# STM32L441CE.net
KiCad netlist of a schematic drawn in EAGLE
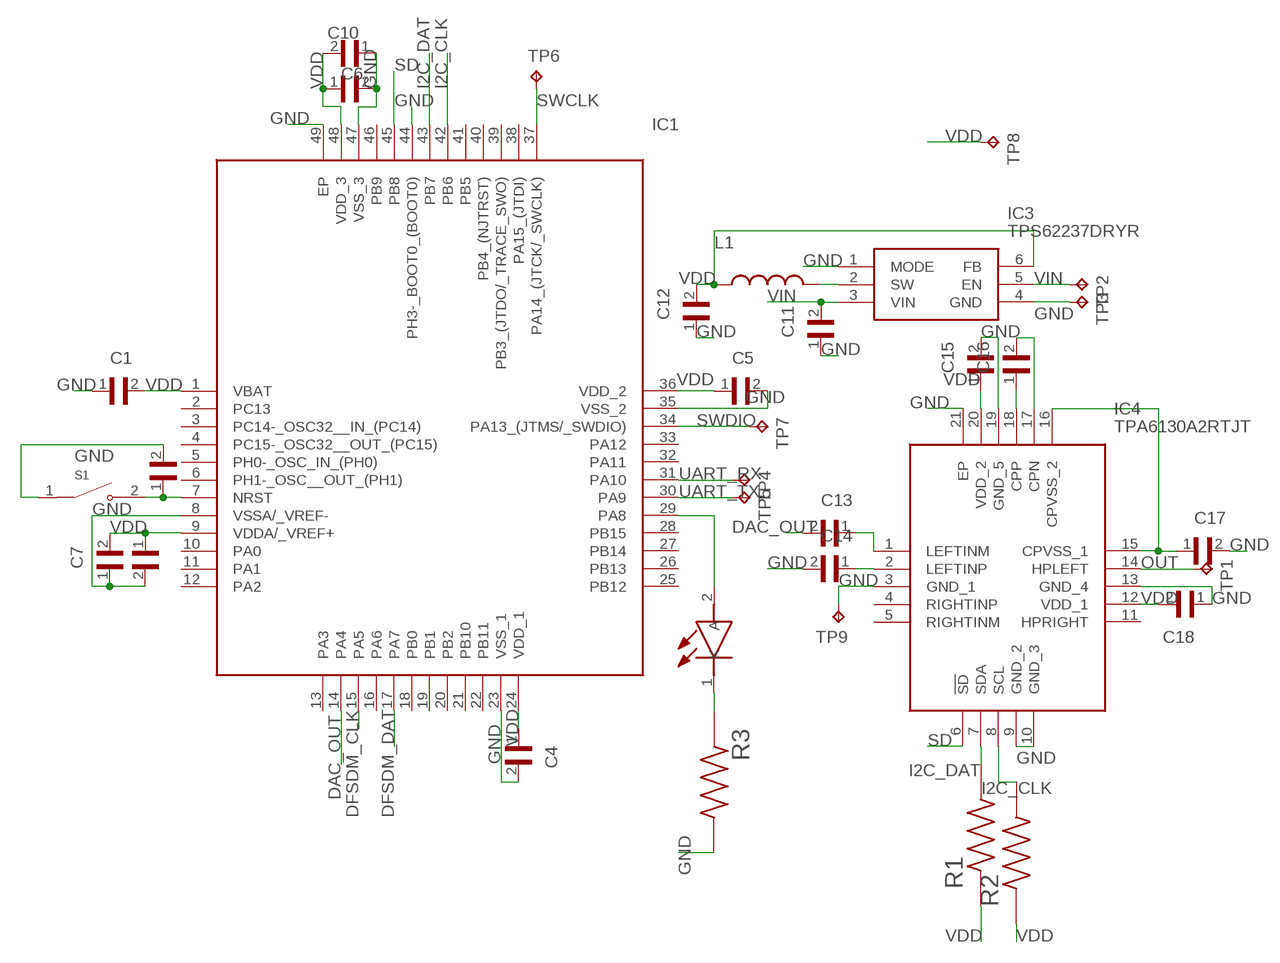
[diagram p0: schematic, sheet 1]
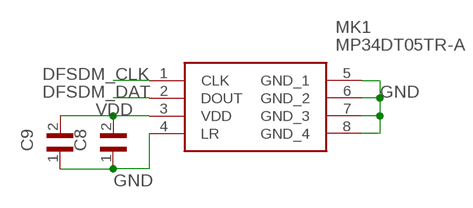
[diagram p1: schematic, sheet 2]

(export (version "E")
  (design (tool "Eeschema 10.0.6"))
  (components
    (comp (ref "C1")
      (value "GRM033C80J104KE15D")
      (footprint "eagle-import:CAPC0603X33N")
      (fields (field (name "DIGI-KEY_PART_NUMBER") "490-10390-1-ND") (field (name "MF") "Murata Electronics"))
      (libsource (lib "eagle-import") (part "GRM033C80J104KE15D"))
    )
    (comp (ref "C2")
      (value "GRM033C80J104KE15D")
      (footprint "eagle-import:CAPC0603X33N")
      (fields (field (name "DIGI-KEY_PART_NUMBER") "490-10390-1-ND") (field (name "MF") "Murata Electronics"))
      (libsource (lib "eagle-import") (part "GRM033C80J104KE15D"))
    )
    (comp (ref "C3")
      (value "GRM033C80J104KE15D")
      (footprint "eagle-import:CAPC0603X33N")
      (fields (field (name "DIGI-KEY_PART_NUMBER") "490-10390-1-ND") (field (name "MF") "Murata Electronics"))
      (libsource (lib "eagle-import") (part "GRM033C80J104KE15D"))
    )
    (comp (ref "C4")
      (value "GRM033C80J104KE15D")
      (footprint "eagle-import:CAPC0603X33N")
      (fields (field (name "DIGI-KEY_PART_NUMBER") "490-10390-1-ND") (field (name "MF") "Murata Electronics"))
      (libsource (lib "eagle-import") (part "GRM033C80J104KE15D"))
    )
    (comp (ref "C5")
      (value "GRM033C80J104KE15D")
      (footprint "eagle-import:CAPC0603X33N")
      (fields (field (name "DIGI-KEY_PART_NUMBER") "490-10390-1-ND") (field (name "MF") "Murata Electronics"))
      (libsource (lib "eagle-import") (part "GRM033C80J104KE15D"))
    )
    (comp (ref "C6")
      (value "GRM033C80J104KE15D")
      (footprint "eagle-import:CAPC0603X33N")
      (fields (field (name "DIGI-KEY_PART_NUMBER") "490-10390-1-ND") (field (name "MF") "Murata Electronics"))
      (libsource (lib "eagle-import") (part "GRM033C80J104KE15D"))
    )
    (comp (ref "C7")
      (value "JMK105C6105KV-F")
      (footprint "eagle-import:CAPC1005X55N")
      (fields (field (name "DIGI-KEY_PART_NUMBER") "587-3381-1-ND") (field (name "MF") "Taiyo Yuden"))
      (libsource (lib "eagle-import") (part "JMK105C6105KV-F"))
    )
    (comp (ref "C10")
      (value "GRM155R60J475ME47D")
      (footprint "eagle-import:CAPC1005X60N")
      (fields (field (name "DIGI-KEY_PART_NUMBER") "490-5915-1-ND") (field (name "MF") "Murata"))
      (libsource (lib "eagle-import") (part "GRM155R60J475ME47D"))
    )
    (comp (ref "C11")
      (value "GRM155R60J225KE95D")
      (footprint "eagle-import:CAPC1005X55N")
      (fields (field (name "DIGI-KEY_PART_NUMBER") "490-12532-1-ND") (field (name "MF") "Murata"))
      (libsource (lib "eagle-import") (part "GRM155R60J225KE95D"))
    )
    (comp (ref "C12")
      (value "GRM155R60J475ME47D")
      (footprint "eagle-import:CAPC1005X60N")
      (fields (field (name "DIGI-KEY_PART_NUMBER") "490-5915-1-ND") (field (name "MF") "Murata"))
      (libsource (lib "eagle-import") (part "GRM155R60J475ME47D"))
    )
    (comp (ref "C13")
      (value "CC0402KRX5R5BB474")
      (footprint "eagle-import:CAPC1005X55N")
      (fields (field (name "DIGI-KEY_PART_NUMBER") "311-1684-1-ND") (field (name "MF") "Yageo"))
      (libsource (lib "eagle-import") (part "CC0402KRX5R5BB474"))
    )
    (comp (ref "C14")
      (value "CC0402KRX5R5BB474")
      (footprint "eagle-import:CAPC1005X55N")
      (fields (field (name "DIGI-KEY_PART_NUMBER") "311-1684-1-ND") (field (name "MF") "Yageo"))
      (libsource (lib "eagle-import") (part "CC0402KRX5R5BB474"))
    )
    (comp (ref "C15")
      (value "JMK105C6105KV-F")
      (footprint "eagle-import:CAPC1005X55N")
      (fields (field (name "DIGI-KEY_PART_NUMBER") "587-3381-1-ND") (field (name "MF") "Taiyo Yuden"))
      (libsource (lib "eagle-import") (part "JMK105C6105KV-F"))
    )
    (comp (ref "C16")
      (value "JMK105C6105KV-F")
      (footprint "eagle-import:CAPC1005X55N")
      (fields (field (name "DIGI-KEY_PART_NUMBER") "587-3381-1-ND") (field (name "MF") "Taiyo Yuden"))
      (libsource (lib "eagle-import") (part "JMK105C6105KV-F"))
    )
    (comp (ref "C17")
      (value "JMK105C6105KV-F")
      (footprint "eagle-import:CAPC1005X55N")
      (fields (field (name "DIGI-KEY_PART_NUMBER") "587-3381-1-ND") (field (name "MF") "Taiyo Yuden"))
      (libsource (lib "eagle-import") (part "JMK105C6105KV-F"))
    )
    (comp (ref "C18")
      (value "JMK105C6105KV-F")
      (footprint "eagle-import:CAPC1005X55N")
      (fields (field (name "DIGI-KEY_PART_NUMBER") "587-3381-1-ND") (field (name "MF") "Taiyo Yuden"))
      (libsource (lib "eagle-import") (part "JMK105C6105KV-F"))
    )
    (comp (ref "IC1")
      (value "STM32L451CEU6")
      (footprint "eagle-import:QFN50P700X700X60-49N")
      (fields (field (name "MOUSER_PART_NUMBER") "511-STM32L451CEU6"))
      (libsource (lib "eagle-import") (part "STM32L451CEU6"))
    )
    (comp (ref "IC3")
      (value "TPS62237DRYR")
      (footprint "eagle-import:SON50P100X145X60-6N")
      (fields (field (name "MOUSER_PART_NUMBER") "595-TPS62237DRYR"))
      (libsource (lib "eagle-import") (part "TPS62237DRYR"))
    )
    (comp (ref "IC4")
      (value "TPA6130A2RTJT")
      (footprint "eagle-import:QFN50P400X400X80-21N")
      (fields (field (name "MOUSER_PART_NUMBER") "595-TPA6130A2RTJT"))
      (libsource (lib "eagle-import") (part "TPA6130A2RTJT"))
    )
    (comp (ref "L1")
      (value "LQM21PN2R2MC0D")
      (footprint "eagle-import:INDC2012X55N")
      (fields (field (name "DIGI-KEY_PART_NUMBER") "490-4994-1-ND") (field (name "MF") "Murata"))
      (libsource (lib "eagle-import") (part "LQM21PN2R2MC0D"))
    )
    (comp (ref "LED1")
      (value "VLMS1500-GS08")
      (footprint "eagle-import:VLMG1500GS08")
      (fields (field (name "MOUSER_PART_NUMBER") "78-VLMS1500-GS08"))
      (libsource (lib "eagle-import") (part "VLMS1500-GS08"))
    )
    (comp (ref "R1")
      (value "ERJ-1GNJ222C")
      (footprint "eagle-import:RESC0603X26N")
      (fields (field (name "DIGI-KEY_PART_NUMBER") "P123277CT-ND") (field (name "MF") "Panasonic"))
      (libsource (lib "eagle-import") (part "ERJ-1GNJ222C"))
    )
    (comp (ref "R2")
      (value "ERJ-1GNJ222C")
      (footprint "eagle-import:RESC0603X26N")
      (fields (field (name "DIGI-KEY_PART_NUMBER") "P123277CT-ND") (field (name "MF") "Panasonic"))
      (libsource (lib "eagle-import") (part "ERJ-1GNJ222C"))
    )
    (comp (ref "R3")
      (value "ERJ-1GNJ222C")
      (footprint "eagle-import:RESC0603X26N")
      (fields (field (name "DIGI-KEY_PART_NUMBER") "P123277CT-ND") (field (name "MF") "Panasonic"))
      (libsource (lib "eagle-import") (part "ERJ-1GNJ222C"))
    )
    (comp (ref "S1")
      (value "B3U-1000P")
      (footprint "eagle-import:SW_B3U-1000P")
      (fields (field (name "DIGI-KEY_PART_NUMBER") "SW1020CT-ND") (field (name "MF") "Omron"))
      (libsource (lib "eagle-import") (part "B3U-1000P"))
    )
    (comp (ref "TP1")
      (value "TPTP11R")
      (footprint "eagle-import:TP11R")
      (libsource (lib "eagle-import") (part "TPTP11R"))
    )
    (comp (ref "TP2")
      (value "TPTP11R")
      (footprint "eagle-import:TP11R")
      (libsource (lib "eagle-import") (part "TPTP11R"))
    )
    (comp (ref "TP3")
      (value "TPTP11R")
      (footprint "eagle-import:TP11R")
      (libsource (lib "eagle-import") (part "TPTP11R"))
    )
    (comp (ref "TP4")
      (value "TPTP11R")
      (footprint "eagle-import:TP11R")
      (libsource (lib "eagle-import") (part "TPTP11R"))
    )
    (comp (ref "TP5")
      (value "TPTP11R")
      (footprint "eagle-import:TP11R")
      (libsource (lib "eagle-import") (part "TPTP11R"))
    )
    (comp (ref "TP6")
      (value "TPTP11R")
      (footprint "eagle-import:TP11R")
      (libsource (lib "eagle-import") (part "TPTP11R"))
    )
    (comp (ref "TP7")
      (value "TPTP11R")
      (footprint "eagle-import:TP11R")
      (libsource (lib "eagle-import") (part "TPTP11R"))
    )
    (comp (ref "TP8")
      (value "TPTP11R")
      (footprint "eagle-import:TP11R")
      (libsource (lib "eagle-import") (part "TPTP11R"))
    )
    (comp (ref "TP9")
      (value "TPTP11R")
      (footprint "eagle-import:TP11R")
      (libsource (lib "eagle-import") (part "TPTP11R"))
    )
    (comp (ref "C8")
      (value "JMK105C6105KV-F")
      (footprint "eagle-import:CAPC1005X55N")
      (fields (field (name "DIGI-KEY_PART_NUMBER") "587-3381-1-ND") (field (name "MF") "Taiyo Yuden"))
      (libsource (lib "eagle-import") (part "JMK105C6105KV-F"))
    )
    (comp (ref "C9")
      (value "GRM033C80J104KE15D")
      (footprint "eagle-import:CAPC0603X33N")
      (fields (field (name "DIGI-KEY_PART_NUMBER") "490-10390-1-ND") (field (name "MF") "Murata Electronics"))
      (libsource (lib "eagle-import") (part "GRM033C80J104KE15D"))
    )
    (comp (ref "MK1")
      (value "MP34DT05TR-A")
      (footprint "eagle-import:MP34DT05TRA")
      (fields (field (name "MOUSER_PART_NUMBER") "511-MP34DT05TR-A"))
      (libsource (lib "eagle-import") (part "MP34DT05TR-A"))
    )
  )
  (nets
    (net (code "1") (name "DAC_OUT") (class "Default")
      (node (ref "C13") (pin "2") (pinfunction "2_2") (pintype "passive"))
      (node (ref "IC1") (pin "14") (pinfunction "PA4_14") (pintype "bidirectional"))
    )
    (net (code "2") (name "DFSDM_CLK") (class "Default")
      (node (ref "IC1") (pin "15") (pinfunction "PA5_15") (pintype "bidirectional"))
      (node (ref "MK1") (pin "1") (pinfunction "CLK_1") (pintype "bidirectional"))
    )
    (net (code "3") (name "DFSDM_DAT") (class "Default")
      (node (ref "IC1") (pin "17") (pinfunction "PA7_17") (pintype "bidirectional"))
      (node (ref "MK1") (pin "2") (pinfunction "DOUT_2") (pintype "bidirectional"))
    )
    (net (code "4") (name "GND") (class "Default")
      (node (ref "C1") (pin "1") (pinfunction "1_1") (pintype "passive"))
      (node (ref "C10") (pin "1") (pinfunction "1_1") (pintype "passive"))
      (node (ref "C11") (pin "1") (pinfunction "1_1") (pintype "passive"))
      (node (ref "C12") (pin "1") (pinfunction "1_1") (pintype "passive"))
      (node (ref "C14") (pin "2") (pinfunction "2_2") (pintype "passive"))
      (node (ref "C15") (pin "2") (pinfunction "2_2") (pintype "passive"))
      (node (ref "C17") (pin "2") (pinfunction "2_2") (pintype "passive"))
      (node (ref "C18") (pin "1") (pinfunction "1_1") (pintype "passive"))
      (node (ref "C2") (pin "2") (pinfunction "2_2") (pintype "passive"))
      (node (ref "C3") (pin "2") (pinfunction "2_2") (pintype "passive"))
      (node (ref "C4") (pin "2") (pinfunction "2_2") (pintype "passive"))
      (node (ref "C5") (pin "2") (pinfunction "2_2") (pintype "passive"))
      (node (ref "C6") (pin "2") (pinfunction "2_2") (pintype "passive"))
      (node (ref "C7") (pin "1") (pinfunction "1_1") (pintype "passive"))
      (node (ref "C8") (pin "1") (pinfunction "1_1") (pintype "passive"))
      (node (ref "C9") (pin "1") (pinfunction "1_1") (pintype "passive"))
      (node (ref "IC1") (pin "23") (pinfunction "VSS_1_23") (pintype "bidirectional"))
      (node (ref "IC1") (pin "35") (pinfunction "VSS_2_35") (pintype "bidirectional"))
      (node (ref "IC1") (pin "44") (pinfunction "PH3-_BOOT0_(BOOT0)_44") (pintype "bidirectional"))
      (node (ref "IC1") (pin "47") (pinfunction "VSS_3_47") (pintype "bidirectional"))
      (node (ref "IC1") (pin "49") (pinfunction "EP_49") (pintype "bidirectional"))
      (node (ref "IC1") (pin "8") (pinfunction "VSSA/_VREF-_8") (pintype "bidirectional"))
      (node (ref "IC3") (pin "1") (pinfunction "MODE_1") (pintype "bidirectional"))
      (node (ref "IC3") (pin "4") (pinfunction "GND_4") (pintype "bidirectional"))
      (node (ref "IC4") (pin "10") (pinfunction "GND_3_10") (pintype "bidirectional"))
      (node (ref "IC4") (pin "13") (pinfunction "GND_4_13") (pintype "bidirectional"))
      (node (ref "IC4") (pin "19") (pinfunction "GND_5_19") (pintype "bidirectional"))
      (node (ref "IC4") (pin "21") (pinfunction "EP_21") (pintype "bidirectional"))
      (node (ref "IC4") (pin "3") (pinfunction "GND_1_3") (pintype "bidirectional"))
      (node (ref "IC4") (pin "9") (pinfunction "GND_2_9") (pintype "bidirectional"))
      (node (ref "MK1") (pin "4") (pinfunction "LR_4") (pintype "bidirectional"))
      (node (ref "MK1") (pin "5") (pinfunction "GND_1_5") (pintype "bidirectional"))
      (node (ref "MK1") (pin "6") (pinfunction "GND_2_6") (pintype "bidirectional"))
      (node (ref "MK1") (pin "7") (pinfunction "GND_3_7") (pintype "bidirectional"))
      (node (ref "MK1") (pin "8") (pinfunction "GND_4_8") (pintype "bidirectional"))
      (node (ref "R3") (pin "2") (pinfunction "2_2") (pintype "passive"))
      (node (ref "S1") (pin "1") (pinfunction "1_1") (pintype "passive"))
      (node (ref "TP3") (pin "TP") (pinfunction "TP_TP") (pintype "input"))
      (node (ref "TP9") (pin "TP") (pinfunction "TP_TP") (pintype "input"))
    )
    (net (code "5") (name "I2C_CLK") (class "Default")
      (node (ref "IC1") (pin "42") (pinfunction "PB6_42") (pintype "bidirectional"))
      (node (ref "IC4") (pin "8") (pinfunction "SCL_8") (pintype "bidirectional"))
      (node (ref "R2") (pin "2") (pinfunction "2_2") (pintype "passive"))
    )
    (net (code "6") (name "I2C_DAT") (class "Default")
      (node (ref "IC1") (pin "43") (pinfunction "PB7_43") (pintype "bidirectional"))
      (node (ref "IC4") (pin "7") (pinfunction "SDA_7") (pintype "bidirectional"))
      (node (ref "R1") (pin "2") (pinfunction "2_2") (pintype "passive"))
    )
    (net (code "7") (name "Net-(IC1-NRST)") (class "Default")
      (node (ref "C2") (pin "1") (pinfunction "1_1") (pintype "passive"))
      (node (ref "IC1") (pin "7") (pinfunction "NRST_7") (pintype "bidirectional"))
      (node (ref "S1") (pin "2") (pinfunction "2_2") (pintype "passive"))
    )
    (net (code "8") (name "Net-(IC1-PA8)") (class "Default")
      (node (ref "IC1") (pin "29") (pinfunction "PA8_29") (pintype "bidirectional"))
      (node (ref "LED1") (pin "2") (pinfunction "A_2") (pintype "bidirectional"))
    )
    (net (code "9") (name "Net-(IC3-SW)") (class "Default")
      (node (ref "IC3") (pin "2") (pinfunction "SW_2") (pintype "bidirectional"))
      (node (ref "L1") (pin "2") (pinfunction "2_2") (pintype "passive"))
    )
    (net (code "10") (name "Net-(IC4-CPN)") (class "Default")
      (node (ref "C16") (pin "2") (pinfunction "2_2") (pintype "passive"))
      (node (ref "IC4") (pin "17") (pinfunction "CPN_17") (pintype "bidirectional"))
    )
    (net (code "11") (name "Net-(IC4-CPP)") (class "Default")
      (node (ref "C16") (pin "1") (pinfunction "1_1") (pintype "passive"))
      (node (ref "IC4") (pin "18") (pinfunction "CPP_18") (pintype "bidirectional"))
    )
    (net (code "12") (name "Net-(IC4-CPVSS_1)") (class "Default")
      (node (ref "C17") (pin "1") (pinfunction "1_1") (pintype "passive"))
      (node (ref "IC4") (pin "15") (pinfunction "CPVSS_1_15") (pintype "bidirectional"))
      (node (ref "IC4") (pin "16") (pinfunction "CPVSS_2_16") (pintype "bidirectional"))
    )
    (net (code "13") (name "Net-(IC4-LEFTINM)") (class "Default")
      (node (ref "C13") (pin "1") (pinfunction "1_1") (pintype "passive"))
      (node (ref "IC4") (pin "1") (pinfunction "LEFTINM_1") (pintype "bidirectional"))
    )
    (net (code "14") (name "Net-(IC4-LEFTINP)") (class "Default")
      (node (ref "C14") (pin "1") (pinfunction "1_1") (pintype "passive"))
      (node (ref "IC4") (pin "2") (pinfunction "LEFTINP_2") (pintype "bidirectional"))
    )
    (net (code "15") (name "Net-(LED1-K)") (class "Default")
      (node (ref "LED1") (pin "1") (pinfunction "K_1") (pintype "bidirectional"))
      (node (ref "R3") (pin "1") (pinfunction "1_1") (pintype "passive"))
    )
    (net (code "16") (name "OUT") (class "Default")
      (node (ref "IC4") (pin "14") (pinfunction "HPLEFT_14") (pintype "bidirectional"))
      (node (ref "TP1") (pin "TP") (pinfunction "TP_TP") (pintype "input"))
    )
    (net (code "17") (name "SD") (class "Default")
      (node (ref "IC1") (pin "45") (pinfunction "PB8_45") (pintype "bidirectional"))
      (node (ref "IC4") (pin "6") (pinfunction "~{SD}_6") (pintype "bidirectional"))
    )
    (net (code "18") (name "SWCLK") (class "Default")
      (node (ref "IC1") (pin "37") (pinfunction "PA14_(JTCK/_SWCLK)_37") (pintype "bidirectional"))
      (node (ref "TP6") (pin "TP") (pinfunction "TP_TP") (pintype "input"))
    )
    (net (code "19") (name "SWDIO") (class "Default")
      (node (ref "IC1") (pin "34") (pinfunction "PA13_(JTMS/_SWDIO)_34") (pintype "bidirectional"))
      (node (ref "TP7") (pin "TP") (pinfunction "TP_TP") (pintype "input"))
    )
    (net (code "20") (name "UART_RX") (class "Default")
      (node (ref "IC1") (pin "31") (pinfunction "PA10_31") (pintype "bidirectional"))
      (node (ref "TP4") (pin "TP") (pinfunction "TP_TP") (pintype "input"))
    )
    (net (code "21") (name "UART_TX") (class "Default")
      (node (ref "IC1") (pin "30") (pinfunction "PA9_30") (pintype "bidirectional"))
      (node (ref "TP5") (pin "TP") (pinfunction "TP_TP") (pintype "input"))
    )
    (net (code "22") (name "VDD") (class "Default")
      (node (ref "C1") (pin "2") (pinfunction "2_2") (pintype "passive"))
      (node (ref "C10") (pin "2") (pinfunction "2_2") (pintype "passive"))
      (node (ref "C12") (pin "2") (pinfunction "2_2") (pintype "passive"))
      (node (ref "C15") (pin "1") (pinfunction "1_1") (pintype "passive"))
      (node (ref "C18") (pin "2") (pinfunction "2_2") (pintype "passive"))
      (node (ref "C3") (pin "1") (pinfunction "1_1") (pintype "passive"))
      (node (ref "C4") (pin "1") (pinfunction "1_1") (pintype "passive"))
      (node (ref "C5") (pin "1") (pinfunction "1_1") (pintype "passive"))
      (node (ref "C6") (pin "1") (pinfunction "1_1") (pintype "passive"))
      (node (ref "C7") (pin "2") (pinfunction "2_2") (pintype "passive"))
      (node (ref "C8") (pin "2") (pinfunction "2_2") (pintype "passive"))
      (node (ref "C9") (pin "2") (pinfunction "2_2") (pintype "passive"))
      (node (ref "IC1") (pin "1") (pinfunction "VBAT_1") (pintype "bidirectional"))
      (node (ref "IC1") (pin "24") (pinfunction "VDD_1_24") (pintype "bidirectional"))
      (node (ref "IC1") (pin "36") (pinfunction "VDD_2_36") (pintype "bidirectional"))
      (node (ref "IC1") (pin "48") (pinfunction "VDD_3_48") (pintype "bidirectional"))
      (node (ref "IC1") (pin "9") (pinfunction "VDDA/_VREF+_9") (pintype "bidirectional"))
      (node (ref "IC3") (pin "6") (pinfunction "FB_6") (pintype "bidirectional"))
      (node (ref "IC4") (pin "12") (pinfunction "VDD_1_12") (pintype "bidirectional"))
      (node (ref "IC4") (pin "20") (pinfunction "VDD_2_20") (pintype "bidirectional"))
      (node (ref "L1") (pin "1") (pinfunction "1_1") (pintype "passive"))
      (node (ref "MK1") (pin "3") (pinfunction "VDD_3") (pintype "bidirectional"))
      (node (ref "R1") (pin "1") (pinfunction "1_1") (pintype "passive"))
      (node (ref "R2") (pin "1") (pinfunction "1_1") (pintype "passive"))
      (node (ref "TP8") (pin "TP") (pinfunction "TP_TP") (pintype "input"))
    )
    (net (code "23") (name "VIN") (class "Default")
      (node (ref "C11") (pin "2") (pinfunction "2_2") (pintype "passive"))
      (node (ref "IC3") (pin "3") (pinfunction "VIN_3") (pintype "bidirectional"))
      (node (ref "IC3") (pin "5") (pinfunction "EN_5") (pintype "bidirectional"))
      (node (ref "TP2") (pin "TP") (pinfunction "TP_TP") (pintype "input"))
    )
    (net (code "24") (name "unconnected-(IC1-PA0-Pad10)") (class "Default")
      (node (ref "IC1") (pin "10") (pinfunction "PA0_10") (pintype "bidirectional"))
    )
    (net (code "25") (name "unconnected-(IC1-PA1-Pad11)") (class "Default")
      (node (ref "IC1") (pin "11") (pinfunction "PA1_11") (pintype "bidirectional"))
    )
    (net (code "26") (name "unconnected-(IC1-PA2-Pad12)") (class "Default")
      (node (ref "IC1") (pin "12") (pinfunction "PA2_12") (pintype "bidirectional"))
    )
    (net (code "27") (name "unconnected-(IC1-PA3-Pad13)") (class "Default")
      (node (ref "IC1") (pin "13") (pinfunction "PA3_13") (pintype "bidirectional"))
    )
    (net (code "28") (name "unconnected-(IC1-PA6-Pad16)") (class "Default")
      (node (ref "IC1") (pin "16") (pinfunction "PA6_16") (pintype "bidirectional"))
    )
    (net (code "29") (name "unconnected-(IC1-PA11-Pad32)") (class "Default")
      (node (ref "IC1") (pin "32") (pinfunction "PA11_32") (pintype "bidirectional"))
    )
    (net (code "30") (name "unconnected-(IC1-PA12-Pad33)") (class "Default")
      (node (ref "IC1") (pin "33") (pinfunction "PA12_33") (pintype "bidirectional"))
    )
    (net (code "31") (name "unconnected-(IC1-PA15_(JTDI)-Pad38)") (class "Default")
      (node (ref "IC1") (pin "38") (pinfunction "PA15_(JTDI)_38") (pintype "bidirectional"))
    )
    (net (code "32") (name "unconnected-(IC1-PB0-Pad18)") (class "Default")
      (node (ref "IC1") (pin "18") (pinfunction "PB0_18") (pintype "bidirectional"))
    )
    (net (code "33") (name "unconnected-(IC1-PB1-Pad19)") (class "Default")
      (node (ref "IC1") (pin "19") (pinfunction "PB1_19") (pintype "bidirectional"))
    )
    (net (code "34") (name "unconnected-(IC1-PB2-Pad20)") (class "Default")
      (node (ref "IC1") (pin "20") (pinfunction "PB2_20") (pintype "bidirectional"))
    )
    (net (code "35") (name "unconnected-(IC1-PB3_(JTDO{slash}_TRACE_SWO)-Pad39)") (class "Default")
      (node (ref "IC1") (pin "39") (pinfunction "PB3_(JTDO/_TRACE_SWO)_39") (pintype "bidirectional"))
    )
    (net (code "36") (name "unconnected-(IC1-PB4_(NJTRST)-Pad40)") (class "Default")
      (node (ref "IC1") (pin "40") (pinfunction "PB4_(NJTRST)_40") (pintype "bidirectional"))
    )
    (net (code "37") (name "unconnected-(IC1-PB5-Pad41)") (class "Default")
      (node (ref "IC1") (pin "41") (pinfunction "PB5_41") (pintype "bidirectional"))
    )
    (net (code "38") (name "unconnected-(IC1-PB9-Pad46)") (class "Default")
      (node (ref "IC1") (pin "46") (pinfunction "PB9_46") (pintype "bidirectional"))
    )
    (net (code "39") (name "unconnected-(IC1-PB10-Pad21)") (class "Default")
      (node (ref "IC1") (pin "21") (pinfunction "PB10_21") (pintype "bidirectional"))
    )
    (net (code "40") (name "unconnected-(IC1-PB11-Pad22)") (class "Default")
      (node (ref "IC1") (pin "22") (pinfunction "PB11_22") (pintype "bidirectional"))
    )
    (net (code "41") (name "unconnected-(IC1-PB12-Pad25)") (class "Default")
      (node (ref "IC1") (pin "25") (pinfunction "PB12_25") (pintype "bidirectional"))
    )
    (net (code "42") (name "unconnected-(IC1-PB13-Pad26)") (class "Default")
      (node (ref "IC1") (pin "26") (pinfunction "PB13_26") (pintype "bidirectional"))
    )
    (net (code "43") (name "unconnected-(IC1-PB14-Pad27)") (class "Default")
      (node (ref "IC1") (pin "27") (pinfunction "PB14_27") (pintype "bidirectional"))
    )
    (net (code "44") (name "unconnected-(IC1-PB15-Pad28)") (class "Default")
      (node (ref "IC1") (pin "28") (pinfunction "PB15_28") (pintype "bidirectional"))
    )
    (net (code "45") (name "unconnected-(IC1-PC13-Pad2)") (class "Default")
      (node (ref "IC1") (pin "2") (pinfunction "PC13_2") (pintype "bidirectional"))
    )
    (net (code "46") (name "unconnected-(IC1-PC14-_OSC32__IN_(PC14)-Pad3)") (class "Default")
      (node (ref "IC1") (pin "3") (pinfunction "PC14-_OSC32__IN_(PC14)_3") (pintype "bidirectional"))
    )
    (net (code "47") (name "unconnected-(IC1-PC15-_OSC32__OUT_(PC15)-Pad4)") (class "Default")
      (node (ref "IC1") (pin "4") (pinfunction "PC15-_OSC32__OUT_(PC15)_4") (pintype "bidirectional"))
    )
    (net (code "48") (name "unconnected-(IC1-PH0-_OSC_IN_(PH0)-Pad5)") (class "Default")
      (node (ref "IC1") (pin "5") (pinfunction "PH0-_OSC_IN_(PH0)_5") (pintype "bidirectional"))
    )
    (net (code "49") (name "unconnected-(IC1-PH1-_OSC__OUT_(PH1)-Pad6)") (class "Default")
      (node (ref "IC1") (pin "6") (pinfunction "PH1-_OSC__OUT_(PH1)_6") (pintype "bidirectional"))
    )
    (net (code "50") (name "unconnected-(IC4-HPRIGHT-Pad11)") (class "Default")
      (node (ref "IC4") (pin "11") (pinfunction "HPRIGHT_11") (pintype "bidirectional"))
    )
    (net (code "51") (name "unconnected-(IC4-RIGHTINM-Pad5)") (class "Default")
      (node (ref "IC4") (pin "5") (pinfunction "RIGHTINM_5") (pintype "bidirectional"))
    )
    (net (code "52") (name "unconnected-(IC4-RIGHTINP-Pad4)") (class "Default")
      (node (ref "IC4") (pin "4") (pinfunction "RIGHTINP_4") (pintype "bidirectional"))
    )
  )
)
